# GENERADORA_V1_5.net
KiCad netlist of a schematic drawn in Altium Designer
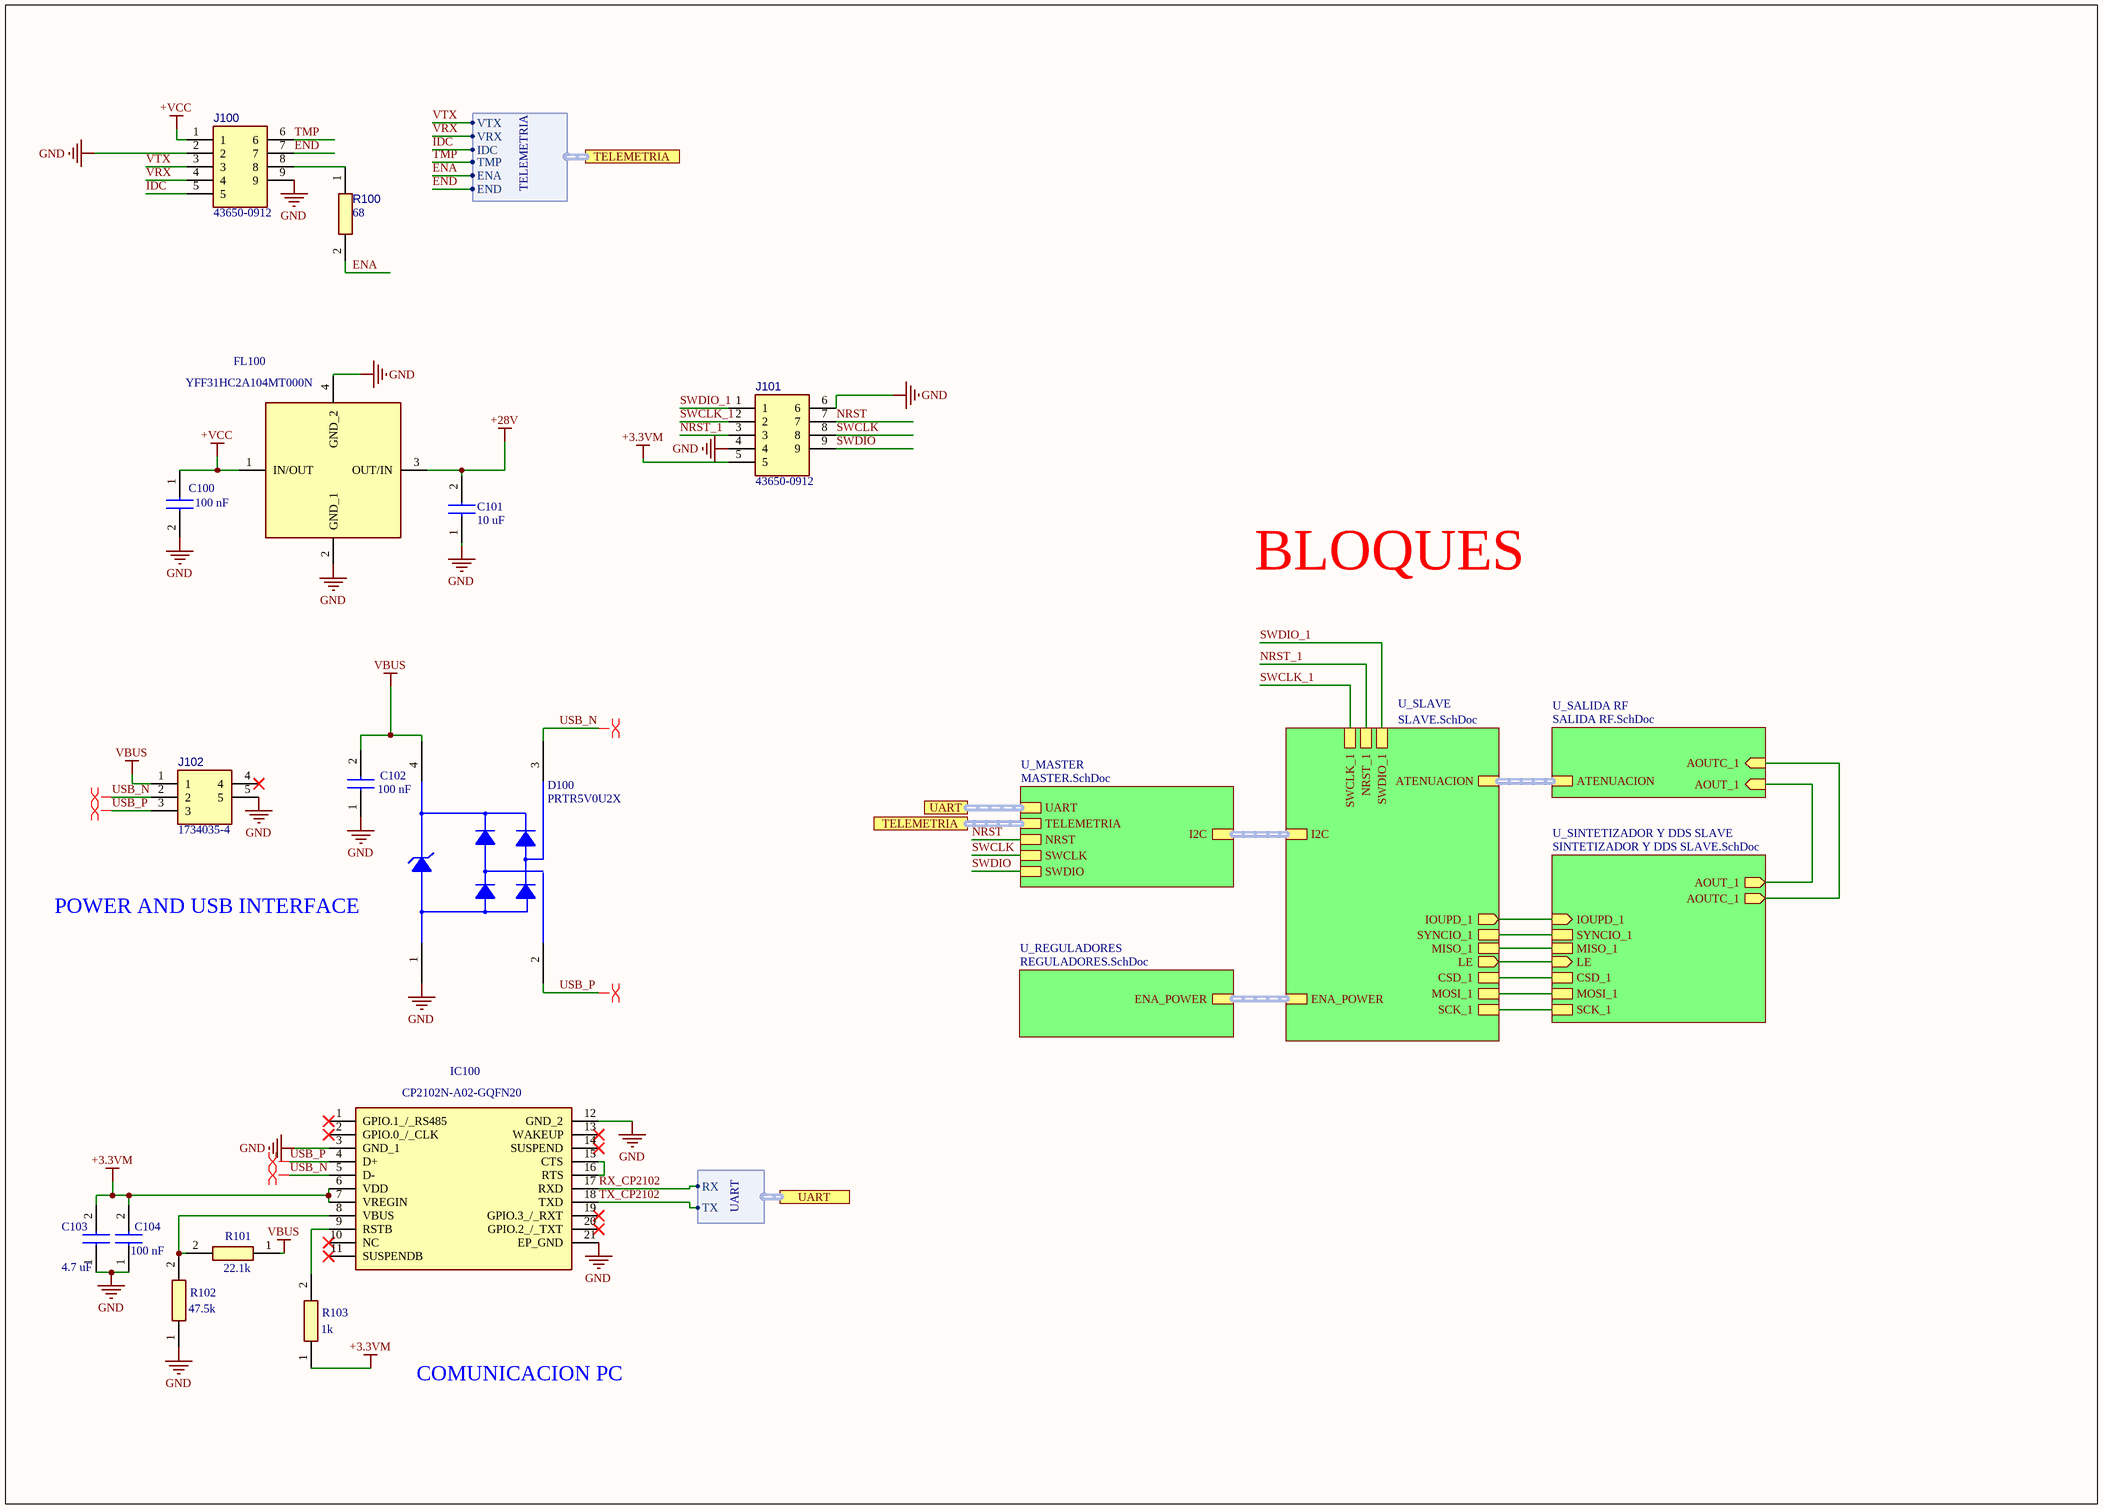
[diagram p0: GENERADORA V1.5.SchDoc]

(export (version "E")
  (design (tool "Eeschema 10.0.6"))
  (components
    (comp (ref "C100")
      (value "100 nF")
      (footprint "SamacSys:CAPC3216X94N")
      (description "Capacitor")
      (fields
        (field (name "MANUFACTURER_PART_NUMBER") "KAM31BR81H103KT")
        (field (name "MOUSER PART NUMBER") "581-KAM31BR81H103KT")
      )
      (libsource (lib "LIBRERIA_GEN_V2.0") (part "KAM31BR81H103KT"))
    )
    (comp (ref "C101")
      (value "10 uF")
      (footprint "SamacSys:CAPC3216X94N")
      (description "Capacitor")
      (fields
        (field (name "MANUFACTURER_PART_NUMBER") "KAM31BR81H103KT")
        (field (name "MOUSER PART NUMBER") "581-KAM31BR81H103KT")
      )
      (libsource (lib "LIBRERIA_GEN_V2.0") (part "KAM31BR81H103KT"))
    )
    (comp (ref "C102")
      (value "100 nF")
      (footprint "SamacSys:CAPC3216X94N")
      (description "Capacitor")
      (fields
        (field (name "MANUFACTURER_PART_NUMBER") "KAM31BR81H103KT")
        (field (name "MOUSER PART NUMBER") "581-KAM31BR81H103KT")
      )
      (libsource (lib "LIBRERIA_GEN_V2.0") (part "KAM31BR81H103KT"))
    )
    (comp (ref "C103")
      (value "4.7 uF")
      (footprint "SamacSys:C0603")
      (description "Capacitor")
      (fields (field (name "MANUFACTURER_PART_NUMBER") "C0603H470J5GACTU"))
      (libsource (lib "LIBRERIA_GEN_V2.0") (part "C0603H470J5GACTU"))
    )
    (comp (ref "C104")
      (value "100 nF")
      (footprint "SamacSys:C0603")
      (description "Capacitor")
      (fields (field (name "MANUFACTURER_PART_NUMBER") "C0603H470J5GACTU"))
      (libsource (lib "LIBRERIA_GEN_V2.0") (part "C0603H470J5GACTU"))
    )
    (comp (ref "D100")
      (value "PRTR5V0U2X")
      (footprint "AP4-00001")
      (description "Double rail-to-rail USB ESD protection diode")
      (fields (field (name "MANUFACTURER") "Philips"))
      (libsource (lib "SAM4S_Xplained_Pro") (part "PRTR5V0U2X"))
    )
    (comp (ref "FL100")
      (value "YFF31HC2A104MT000N")
      (footprint "SamacSys:YFF31HC2A104MT000N")
      (description "Filter")
      (fields (field (name "MOUSER PART NUMBER") "810-YFF31HC2A104MTHN"))
      (libsource (lib "LIBRERIA_GEN_V2.0") (part "YFF31HC2A104MT000N"))
    )
    (comp (ref "IC100")
      (value "CP2102N-A02-GQFN20")
      (footprint "SamacSys:CP2102NA02GQFN20")
      (description "Integrated Circuit")
      (fields (field (name "MOUSER PART NUMBER") "634-CP2102NA02GQFN20"))
      (libsource (lib "LIBRERIA_GEN_V2.0") (part "CP2102N-A02-GQFN20"))
    )
    (comp (ref "J100")
      (value "43650-0912")
      (footprint "SamacSys:43650-09(12,13,14)")
      (description "Connector")
      (fields (field (name "MOUSER PART NUMBER") "538-43650-0912"))
      (libsource (lib "*") (part "43650-0912"))
    )
    (comp (ref "J101")
      (value "43650-0912")
      (footprint "SamacSys:43650-09(12,13,14)")
      (description "Connector")
      (fields (field (name "MOUSER PART NUMBER") "538-43650-0912"))
      (libsource (lib "*") (part "43650-0912"))
    )
    (comp (ref "J102")
      (value "1734035-4")
      (footprint "SamacSys:1734035-2USB")
      (description "Connector")
      (fields (field (name "MOUSER PART NUMBER") "571-1734035-4"))
      (libsource (lib "SamacSys") (part "1734035-4"))
    )
    (comp (ref "R100")
      (value "68")
      (footprint "SamacSys:RESC1608X55N")
      (description "Resistor")
      (fields
        (field (name "MANUFACTURER_PART_NUMBER") "CR0603-FX-1431ELF")
        (field (name "MOUSER PART NUMBER") "652-CR0603FX-1431ELF")
      )
      (libsource (lib "*") (part "CR0603-FX-1431ELF"))
    )
    (comp (ref "R101")
      (value "22.1k")
      (footprint "SamacSys:RESC1608X55N")
      (description "Resistor")
      (fields
        (field (name "MANUFACTURER_PART_NUMBER") "CR0603-FX-1431ELF")
        (field (name "MOUSER PART NUMBER") "652-CR0603FX-1431ELF")
      )
      (libsource (lib "LIBRERIA_GEN_V2.0") (part "CR0603-FX-1431ELF"))
    )
    (comp (ref "R102")
      (value "47.5k")
      (footprint "SamacSys:RESC1608X55N")
      (description "Resistor")
      (fields
        (field (name "MANUFACTURER_PART_NUMBER") "CR0603-FX-1431ELF")
        (field (name "MOUSER PART NUMBER") "652-CR0603FX-1431ELF")
      )
      (libsource (lib "") (part "CR0603-FX-1431ELF_1"))
    )
    (comp (ref "R103")
      (value "1k")
      (footprint "SamacSys:RESC1608X55N")
      (description "Resistor")
      (fields
        (field (name "MANUFACTURER_PART_NUMBER") "CR0603-FX-1431ELF")
        (field (name "MOUSER PART NUMBER") "652-CR0603FX-1431ELF")
      )
      (libsource (lib "") (part "CR0603-FX-1431ELF_1"))
    )
  )
  (nets
    (net (code "4") (name "+3.3VM") (class "Default")
      (node (ref "C103") (pin "2") (pinfunction "2_2") (pintype "passive"))
      (node (ref "C104") (pin "2") (pinfunction "2_2") (pintype "passive"))
      (node (ref "IC100") (pin "6") (pinfunction "VDD_6") (pintype "passive"))
      (node (ref "IC100") (pin "7") (pinfunction "VREGIN_7") (pintype "passive"))
      (node (ref "J101") (pin "5") (pinfunction "5_5") (pintype "passive"))
      (node (ref "R103") (pin "1") (pinfunction "1_1") (pintype "passive"))
    )
    (net (code "5") (name "+28V") (class "Default")
      (node (ref "C101") (pin "2") (pinfunction "2_2") (pintype "passive"))
      (node (ref "FL100") (pin "3") (pinfunction "OUT/IN_3") (pintype "passive"))
    )
    (net (code "6") (name "+VCC") (class "Default")
      (node (ref "C100") (pin "1") (pinfunction "1_1") (pintype "passive"))
      (node (ref "FL100") (pin "1") (pinfunction "IN/OUT_1") (pintype "passive"))
      (node (ref "J100") (pin "1") (pinfunction "1_1") (pintype "passive"))
    )
    (net (code "11") (name "/ENA") (class "Default")
      (node (ref "R100") (pin "2") (pinfunction "2_2") (pintype "passive"))
    )
    (net (code "13") (name "/END") (class "Default")
      (node (ref "J100") (pin "7") (pinfunction "7_7") (pintype "passive"))
    )
    (net (code "15") (name "/IDC") (class "Default")
      (node (ref "J100") (pin "5") (pinfunction "5_5") (pintype "passive"))
    )
    (net (code "20") (name "/NRST") (class "Default")
      (node (ref "J101") (pin "7") (pinfunction "7_7") (pintype "passive"))
    )
    (net (code "21") (name "/NRST_1") (class "Default")
      (node (ref "J101") (pin "3") (pinfunction "3_3") (pintype "passive"))
    )
    (net (code "22") (name "/RX_CP2102") (class "Default")
      (node (ref "IC100") (pin "17") (pinfunction "RXD_17") (pintype "passive"))
    )
    (net (code "24") (name "/SWCLK") (class "Default")
      (node (ref "J101") (pin "8") (pinfunction "8_8") (pintype "passive"))
    )
    (net (code "25") (name "/SWCLK_1") (class "Default")
      (node (ref "J101") (pin "2") (pinfunction "2_2") (pintype "passive"))
    )
    (net (code "26") (name "/SWDIO") (class "Default")
      (node (ref "J101") (pin "9") (pinfunction "9_9") (pintype "passive"))
    )
    (net (code "27") (name "/SWDIO_1") (class "Default")
      (node (ref "J101") (pin "1") (pinfunction "1_1") (pintype "passive"))
    )
    (net (code "29") (name "/TMP") (class "Default")
      (node (ref "J100") (pin "6") (pinfunction "6_6") (pintype "passive"))
    )
    (net (code "30") (name "/TX_CP2102") (class "Default")
      (node (ref "IC100") (pin "18") (pinfunction "TXD_18") (pintype "passive"))
    )
    (net (code "32") (name "/USB_N") (class "Default")
      (node (ref "D100") (pin "3") (pinfunction "I/O_2_3") (pintype "passive"))
      (node (ref "IC100") (pin "5") (pinfunction "D-_5") (pintype "passive"))
      (node (ref "J102") (pin "2") (pinfunction "2_2") (pintype "passive"))
    )
    (net (code "33") (name "/USB_P") (class "Default")
      (node (ref "D100") (pin "2") (pinfunction "I/O_1_2") (pintype "passive"))
      (node (ref "IC100") (pin "4") (pinfunction "D+_4") (pintype "passive"))
      (node (ref "J102") (pin "3") (pinfunction "3_3") (pintype "passive"))
    )
    (net (code "34") (name "/VRX") (class "Default")
      (node (ref "J100") (pin "4") (pinfunction "4_4") (pintype "passive"))
    )
    (net (code "35") (name "/VTX") (class "Default")
      (node (ref "J100") (pin "3") (pinfunction "3_3") (pintype "passive"))
    )
    (net (code "38") (name "GND") (class "Default")
      (node (ref "C100") (pin "2") (pinfunction "2_2") (pintype "passive"))
      (node (ref "C101") (pin "1") (pinfunction "1_1") (pintype "passive"))
      (node (ref "C102") (pin "1") (pinfunction "1_1") (pintype "passive"))
      (node (ref "C103") (pin "1") (pinfunction "1_1") (pintype "passive"))
      (node (ref "C104") (pin "1") (pinfunction "1_1") (pintype "passive"))
      (node (ref "D100") (pin "1") (pinfunction "GND_1") (pintype "passive"))
      (node (ref "FL100") (pin "2") (pinfunction "GND_1_2") (pintype "passive"))
      (node (ref "FL100") (pin "4") (pinfunction "GND_2_4") (pintype "passive"))
      (node (ref "IC100") (pin "12") (pinfunction "GND_2_12") (pintype "passive"))
      (node (ref "IC100") (pin "21") (pinfunction "EP_GND_21") (pintype "passive"))
      (node (ref "IC100") (pin "3") (pinfunction "GND_1_3") (pintype "passive"))
      (node (ref "J100") (pin "2") (pinfunction "2_2") (pintype "passive"))
      (node (ref "J100") (pin "9") (pinfunction "9_9") (pintype "passive"))
      (node (ref "J101") (pin "4") (pinfunction "4_4") (pintype "passive"))
      (node (ref "J101") (pin "6") (pinfunction "6_6") (pintype "passive"))
      (node (ref "J102") (pin "5") (pinfunction "5_5") (pintype "passive"))
      (node (ref "R102") (pin "1") (pinfunction "1_1") (pintype "passive"))
    )
    (net (code "39") (name "Net-(IC100-CTS)") (class "Default")
      (node (ref "IC100") (pin "15") (pinfunction "CTS_15") (pintype "passive"))
      (node (ref "IC100") (pin "16") (pinfunction "RTS_16") (pintype "passive"))
    )
    (net (code "40") (name "Net-(IC100-RSTB)") (class "Default")
      (node (ref "IC100") (pin "9") (pinfunction "RSTB_9") (pintype "passive"))
      (node (ref "R103") (pin "2") (pinfunction "2_2") (pintype "passive"))
    )
    (net (code "41") (name "Net-(IC100-VBUS)") (class "Default")
      (node (ref "IC100") (pin "8") (pinfunction "VBUS_8") (pintype "passive"))
      (node (ref "R101") (pin "2") (pinfunction "2_2") (pintype "passive"))
      (node (ref "R102") (pin "2") (pinfunction "2_2") (pintype "passive"))
    )
    (net (code "42") (name "Net-(J100-Pad8)") (class "Default")
      (node (ref "J100") (pin "8") (pinfunction "8_8") (pintype "passive"))
      (node (ref "R100") (pin "1") (pinfunction "1_1") (pintype "passive"))
    )
    (net (code "43") (name "VBUS") (class "Default")
      (node (ref "C102") (pin "2") (pinfunction "2_2") (pintype "passive"))
      (node (ref "D100") (pin "4") (pinfunction "VCC_4") (pintype "passive"))
      (node (ref "J102") (pin "1") (pinfunction "1_1") (pintype "passive"))
      (node (ref "R101") (pin "1") (pinfunction "1_1") (pintype "passive"))
    )
    (net (code "44") (name "unconnected-(IC100-GPIO.0_{slash}_CLK-Pad2)") (class "Default")
      (node (ref "IC100") (pin "2") (pinfunction "GPIO.0_/_CLK_2") (pintype "passive+no_connect"))
    )
    (net (code "45") (name "unconnected-(IC100-GPIO.1_{slash}_RS485-Pad1)") (class "Default")
      (node (ref "IC100") (pin "1") (pinfunction "GPIO.1_/_RS485_1") (pintype "passive+no_connect"))
    )
    (net (code "46") (name "unconnected-(IC100-GPIO.2_{slash}_TXT-Pad20)") (class "Default")
      (node (ref "IC100") (pin "20") (pinfunction "GPIO.2_/_TXT_20") (pintype "passive+no_connect"))
    )
    (net (code "47") (name "unconnected-(IC100-GPIO.3_{slash}_RXT-Pad19)") (class "Default")
      (node (ref "IC100") (pin "19") (pinfunction "GPIO.3_/_RXT_19") (pintype "passive+no_connect"))
    )
    (net (code "48") (name "unconnected-(IC100-NC-Pad10)") (class "Default")
      (node (ref "IC100") (pin "10") (pinfunction "NC_10") (pintype "passive+no_connect"))
    )
    (net (code "49") (name "unconnected-(IC100-SUSPEND-Pad14)") (class "Default")
      (node (ref "IC100") (pin "14") (pinfunction "SUSPEND_14") (pintype "passive+no_connect"))
    )
    (net (code "50") (name "unconnected-(IC100-SUSPENDB-Pad11)") (class "Default")
      (node (ref "IC100") (pin "11") (pinfunction "SUSPENDB_11") (pintype "passive+no_connect"))
    )
    (net (code "51") (name "unconnected-(IC100-WAKEUP-Pad13)") (class "Default")
      (node (ref "IC100") (pin "13") (pinfunction "WAKEUP_13") (pintype "passive+no_connect"))
    )
    (net (code "52") (name "unconnected-(J102-Pad4)") (class "Default")
      (node (ref "J102") (pin "4") (pinfunction "4_4") (pintype "passive+no_connect"))
    )
  )
)
